# BehaviorShield-PowerEnable-DB9.net
KiCad netlist of a schematic drawn in EAGLE
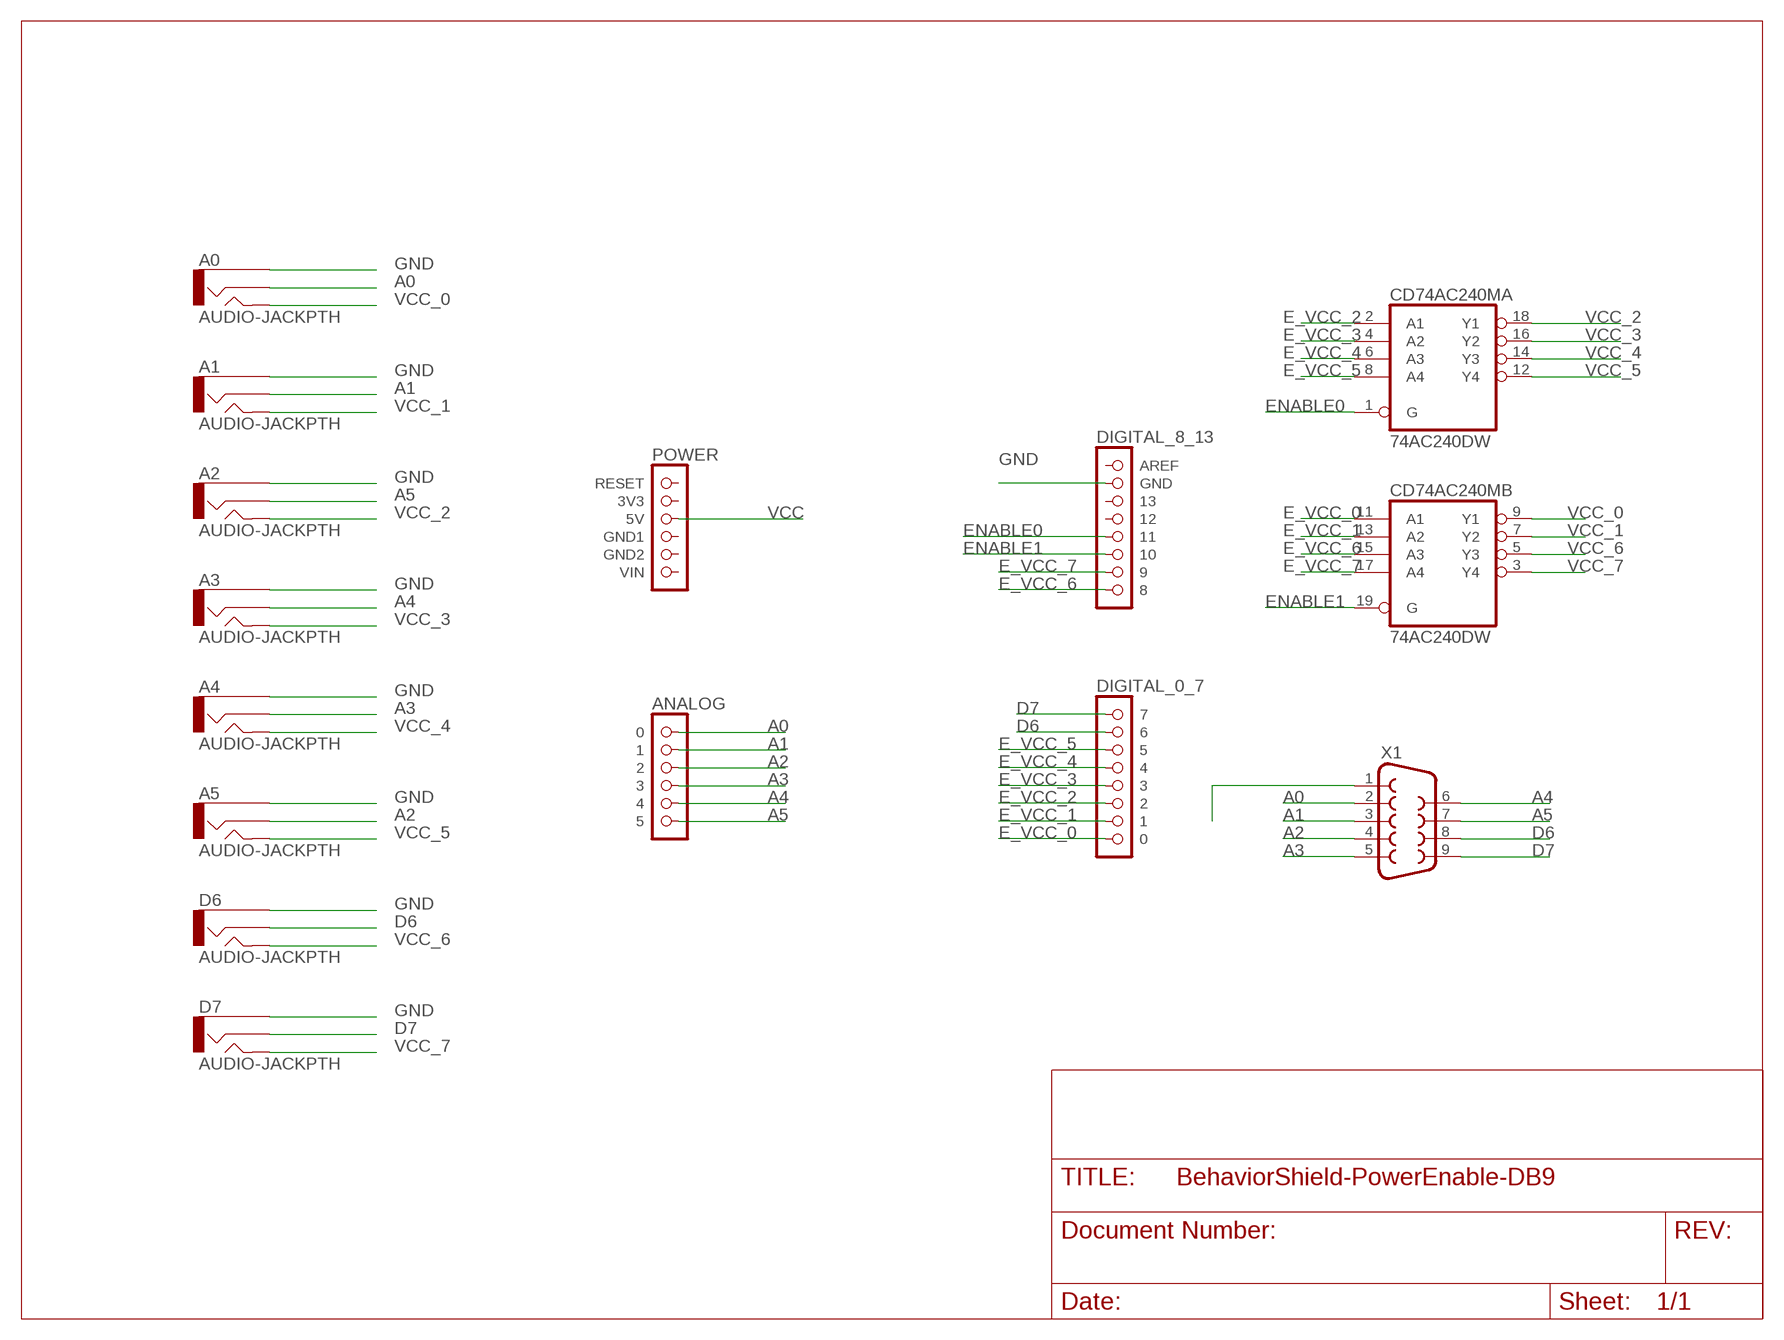
[diagram p0: schematic, sheet 1]

(export (version "E")
  (design (tool "Eeschema 10.0.6"))
  (components
    (comp (ref "A0")
      (value "AUDIO-JACKPTH")
      (footprint "eagle-import:AUDIO-JACK")
      (libsource (lib "eagle-import") (part "AUDIO-JACKPTH"))
    )
    (comp (ref "A1")
      (value "AUDIO-JACKPTH")
      (footprint "eagle-import:AUDIO-JACK")
      (libsource (lib "eagle-import") (part "AUDIO-JACKPTH"))
    )
    (comp (ref "A2")
      (value "AUDIO-JACKPTH")
      (footprint "eagle-import:AUDIO-JACK")
      (libsource (lib "eagle-import") (part "AUDIO-JACKPTH"))
    )
    (comp (ref "A3")
      (value "AUDIO-JACKPTH")
      (footprint "eagle-import:AUDIO-JACK")
      (libsource (lib "eagle-import") (part "AUDIO-JACKPTH"))
    )
    (comp (ref "A4")
      (value "AUDIO-JACKPTH")
      (footprint "eagle-import:AUDIO-JACK")
      (libsource (lib "eagle-import") (part "AUDIO-JACKPTH"))
    )
    (comp (ref "A5")
      (value "AUDIO-JACKPTH")
      (footprint "eagle-import:AUDIO-JACK")
      (libsource (lib "eagle-import") (part "AUDIO-JACKPTH"))
    )
    (comp (ref "CD74AC240M")
      (value "74AC240DW")
      (footprint "eagle-import:SO20W")
      (libsource (lib "eagle-import") (part "74240DWAC"))
    )
    (comp (ref "D6")
      (value "AUDIO-JACKPTH")
      (footprint "eagle-import:AUDIO-JACK")
      (libsource (lib "eagle-import") (part "AUDIO-JACKPTH"))
    )
    (comp (ref "D7")
      (value "AUDIO-JACKPTH")
      (footprint "eagle-import:AUDIO-JACK")
      (libsource (lib "eagle-import") (part "AUDIO-JACKPTH"))
    )
    (comp (ref "U$1")
      (value "POWER")
      (footprint "eagle-import:1X06")
      (libsource (lib "eagle-import") (part "POWER"))
    )
    (comp (ref "U$2")
      (value "ANALOG")
      (footprint "eagle-import:1X06")
      (libsource (lib "eagle-import") (part "ANALOG"))
    )
    (comp (ref "U$3")
      (value "DIGITAL_0_7")
      (footprint "eagle-import:1X08")
      (libsource (lib "eagle-import") (part "DIGITAL_0_7"))
    )
    (comp (ref "U$4")
      (value "DIGITAL_8_13")
      (footprint "eagle-import:1X08")
      (libsource (lib "eagle-import") (part "DIGITAL_8_13"))
    )
    (comp (ref "X1")
      (value "F09HP")
      (footprint "eagle-import:F09HP")
      (libsource (lib "eagle-import") (part "F09HP"))
    )
  )
  (nets
    (net (code "1") (name "/A0") (class "Default")
      (node (ref "A0") (pin "2") (pinfunction "2_2") (pintype "bidirectional"))
      (node (ref "U$2") (pin "1") (pinfunction "0_1") (pintype "passive"))
      (node (ref "X1") (pin "2") (pinfunction "2_2") (pintype "passive"))
    )
    (net (code "2") (name "/A1") (class "Default")
      (node (ref "A1") (pin "2") (pinfunction "2_2") (pintype "bidirectional"))
      (node (ref "U$2") (pin "2") (pinfunction "1_2") (pintype "passive"))
      (node (ref "X1") (pin "3") (pinfunction "3_3") (pintype "passive"))
    )
    (net (code "3") (name "/A2") (class "Default")
      (node (ref "A5") (pin "2") (pinfunction "2_2") (pintype "bidirectional"))
      (node (ref "U$2") (pin "3") (pinfunction "2_3") (pintype "passive"))
      (node (ref "X1") (pin "4") (pinfunction "4_4") (pintype "passive"))
    )
    (net (code "4") (name "/A3") (class "Default")
      (node (ref "A4") (pin "2") (pinfunction "2_2") (pintype "bidirectional"))
      (node (ref "U$2") (pin "4") (pinfunction "3_4") (pintype "passive"))
      (node (ref "X1") (pin "5") (pinfunction "5_5") (pintype "passive"))
    )
    (net (code "5") (name "/A4") (class "Default")
      (node (ref "A3") (pin "2") (pinfunction "2_2") (pintype "bidirectional"))
      (node (ref "U$2") (pin "5") (pinfunction "4_5") (pintype "passive"))
      (node (ref "X1") (pin "6") (pinfunction "6_6") (pintype "passive"))
    )
    (net (code "6") (name "/A5") (class "Default")
      (node (ref "A2") (pin "2") (pinfunction "2_2") (pintype "bidirectional"))
      (node (ref "U$2") (pin "6") (pinfunction "5_6") (pintype "passive"))
      (node (ref "X1") (pin "7") (pinfunction "7_7") (pintype "passive"))
    )
    (net (code "7") (name "/D6") (class "Default")
      (node (ref "D6") (pin "2") (pinfunction "2_2") (pintype "bidirectional"))
      (node (ref "U$3") (pin "2") (pinfunction "6_2") (pintype "passive"))
      (node (ref "X1") (pin "8") (pinfunction "8_8") (pintype "passive"))
    )
    (net (code "8") (name "/D7") (class "Default")
      (node (ref "D7") (pin "2") (pinfunction "2_2") (pintype "bidirectional"))
      (node (ref "U$3") (pin "1") (pinfunction "7_1") (pintype "passive"))
      (node (ref "X1") (pin "9") (pinfunction "9_9") (pintype "passive"))
    )
    (net (code "9") (name "/ENABLE0") (class "Default")
      (node (ref "CD74AC240M") (pin "1") (pinfunction "G_1") (pintype "input"))
      (node (ref "U$4") (pin "5") (pinfunction "11_5") (pintype "passive"))
    )
    (net (code "10") (name "/ENABLE1") (class "Default")
      (node (ref "CD74AC240M") (pin "19") (pinfunction "G_19") (pintype "input"))
      (node (ref "U$4") (pin "6") (pinfunction "10_6") (pintype "passive"))
    )
    (net (code "11") (name "/E_VCC_0") (class "Default")
      (node (ref "CD74AC240M") (pin "11") (pinfunction "A1_11") (pintype "input"))
      (node (ref "U$3") (pin "8") (pinfunction "0_8") (pintype "passive"))
    )
    (net (code "12") (name "/E_VCC_1") (class "Default")
      (node (ref "CD74AC240M") (pin "13") (pinfunction "A2_13") (pintype "input"))
      (node (ref "U$3") (pin "7") (pinfunction "1_7") (pintype "passive"))
    )
    (net (code "13") (name "/E_VCC_2") (class "Default")
      (node (ref "CD74AC240M") (pin "2") (pinfunction "A1_2") (pintype "input"))
      (node (ref "U$3") (pin "6") (pinfunction "2_6") (pintype "passive"))
    )
    (net (code "14") (name "/E_VCC_3") (class "Default")
      (node (ref "CD74AC240M") (pin "4") (pinfunction "A2_4") (pintype "input"))
      (node (ref "U$3") (pin "5") (pinfunction "3_5") (pintype "passive"))
    )
    (net (code "15") (name "/E_VCC_4") (class "Default")
      (node (ref "CD74AC240M") (pin "6") (pinfunction "A3_6") (pintype "input"))
      (node (ref "U$3") (pin "4") (pinfunction "4_4") (pintype "passive"))
    )
    (net (code "16") (name "/E_VCC_5") (class "Default")
      (node (ref "CD74AC240M") (pin "8") (pinfunction "A4_8") (pintype "input"))
      (node (ref "U$3") (pin "3") (pinfunction "5_3") (pintype "passive"))
    )
    (net (code "17") (name "/E_VCC_6") (class "Default")
      (node (ref "CD74AC240M") (pin "15") (pinfunction "A3_15") (pintype "input"))
      (node (ref "U$4") (pin "8") (pinfunction "8_8") (pintype "passive"))
    )
    (net (code "18") (name "/E_VCC_7") (class "Default")
      (node (ref "CD74AC240M") (pin "17") (pinfunction "A4_17") (pintype "input"))
      (node (ref "U$4") (pin "7") (pinfunction "9_7") (pintype "passive"))
    )
    (net (code "19") (name "/GND") (class "Default")
      (node (ref "A0") (pin "1") (pinfunction "1_1") (pintype "bidirectional"))
      (node (ref "A1") (pin "1") (pinfunction "1_1") (pintype "bidirectional"))
      (node (ref "A2") (pin "1") (pinfunction "1_1") (pintype "bidirectional"))
      (node (ref "A3") (pin "1") (pinfunction "1_1") (pintype "bidirectional"))
      (node (ref "A4") (pin "1") (pinfunction "1_1") (pintype "bidirectional"))
      (node (ref "A5") (pin "1") (pinfunction "1_1") (pintype "bidirectional"))
      (node (ref "D6") (pin "1") (pinfunction "1_1") (pintype "bidirectional"))
      (node (ref "D7") (pin "1") (pinfunction "1_1") (pintype "bidirectional"))
      (node (ref "U$4") (pin "2") (pinfunction "GND_2") (pintype "passive"))
      (node (ref "X1") (pin "1") (pinfunction "1_1") (pintype "passive"))
    )
    (net (code "20") (name "/VCC") (class "Default")
      (node (ref "U$1") (pin "3") (pinfunction "5V_3") (pintype "passive"))
    )
    (net (code "21") (name "/VCC_0") (class "Default")
      (node (ref "A0") (pin "5") (pinfunction "5_5") (pintype "bidirectional"))
      (node (ref "CD74AC240M") (pin "9") (pinfunction "Y1_9") (pintype "tri_state"))
    )
    (net (code "22") (name "/VCC_1") (class "Default")
      (node (ref "A1") (pin "5") (pinfunction "5_5") (pintype "bidirectional"))
      (node (ref "CD74AC240M") (pin "7") (pinfunction "Y2_7") (pintype "tri_state"))
    )
    (net (code "23") (name "/VCC_2") (class "Default")
      (node (ref "A2") (pin "5") (pinfunction "5_5") (pintype "bidirectional"))
      (node (ref "CD74AC240M") (pin "18") (pinfunction "Y1_18") (pintype "tri_state"))
    )
    (net (code "24") (name "/VCC_3") (class "Default")
      (node (ref "A3") (pin "5") (pinfunction "5_5") (pintype "bidirectional"))
      (node (ref "CD74AC240M") (pin "16") (pinfunction "Y2_16") (pintype "tri_state"))
    )
    (net (code "25") (name "/VCC_4") (class "Default")
      (node (ref "A4") (pin "5") (pinfunction "5_5") (pintype "bidirectional"))
      (node (ref "CD74AC240M") (pin "14") (pinfunction "Y3_14") (pintype "tri_state"))
    )
    (net (code "26") (name "/VCC_5") (class "Default")
      (node (ref "A5") (pin "5") (pinfunction "5_5") (pintype "bidirectional"))
      (node (ref "CD74AC240M") (pin "12") (pinfunction "Y4_12") (pintype "tri_state"))
    )
    (net (code "27") (name "/VCC_6") (class "Default")
      (node (ref "CD74AC240M") (pin "5") (pinfunction "Y3_5") (pintype "tri_state"))
      (node (ref "D6") (pin "5") (pinfunction "5_5") (pintype "bidirectional"))
    )
    (net (code "28") (name "/VCC_7") (class "Default")
      (node (ref "CD74AC240M") (pin "3") (pinfunction "Y4_3") (pintype "tri_state"))
      (node (ref "D7") (pin "5") (pinfunction "5_5") (pintype "bidirectional"))
    )
    (net (code "29") (name "unconnected-(U$1-3V3-Pad2)") (class "Default")
      (node (ref "U$1") (pin "2") (pinfunction "3V3_2") (pintype "passive"))
    )
    (net (code "30") (name "unconnected-(U$1-GND1-Pad4)") (class "Default")
      (node (ref "U$1") (pin "4") (pinfunction "GND1_4") (pintype "passive"))
    )
    (net (code "31") (name "unconnected-(U$1-GND2-Pad5)") (class "Default")
      (node (ref "U$1") (pin "5") (pinfunction "GND2_5") (pintype "passive"))
    )
    (net (code "32") (name "unconnected-(U$1-RESET-Pad1)") (class "Default")
      (node (ref "U$1") (pin "1") (pinfunction "RESET_1") (pintype "passive"))
    )
    (net (code "33") (name "unconnected-(U$1-VIN-Pad6)") (class "Default")
      (node (ref "U$1") (pin "6") (pinfunction "VIN_6") (pintype "passive"))
    )
    (net (code "34") (name "unconnected-(U$4-12-Pad4)") (class "Default")
      (node (ref "U$4") (pin "4") (pinfunction "12_4") (pintype "passive"))
    )
    (net (code "35") (name "unconnected-(U$4-13-Pad3)") (class "Default")
      (node (ref "U$4") (pin "3") (pinfunction "13_3") (pintype "passive"))
    )
    (net (code "36") (name "unconnected-(U$4-AREF-Pad1)") (class "Default")
      (node (ref "U$4") (pin "1") (pinfunction "AREF_1") (pintype "passive"))
    )
  )
)
